# tx-warmer-smd.net
KiCad netlist of a schematic drawn in EAGLE
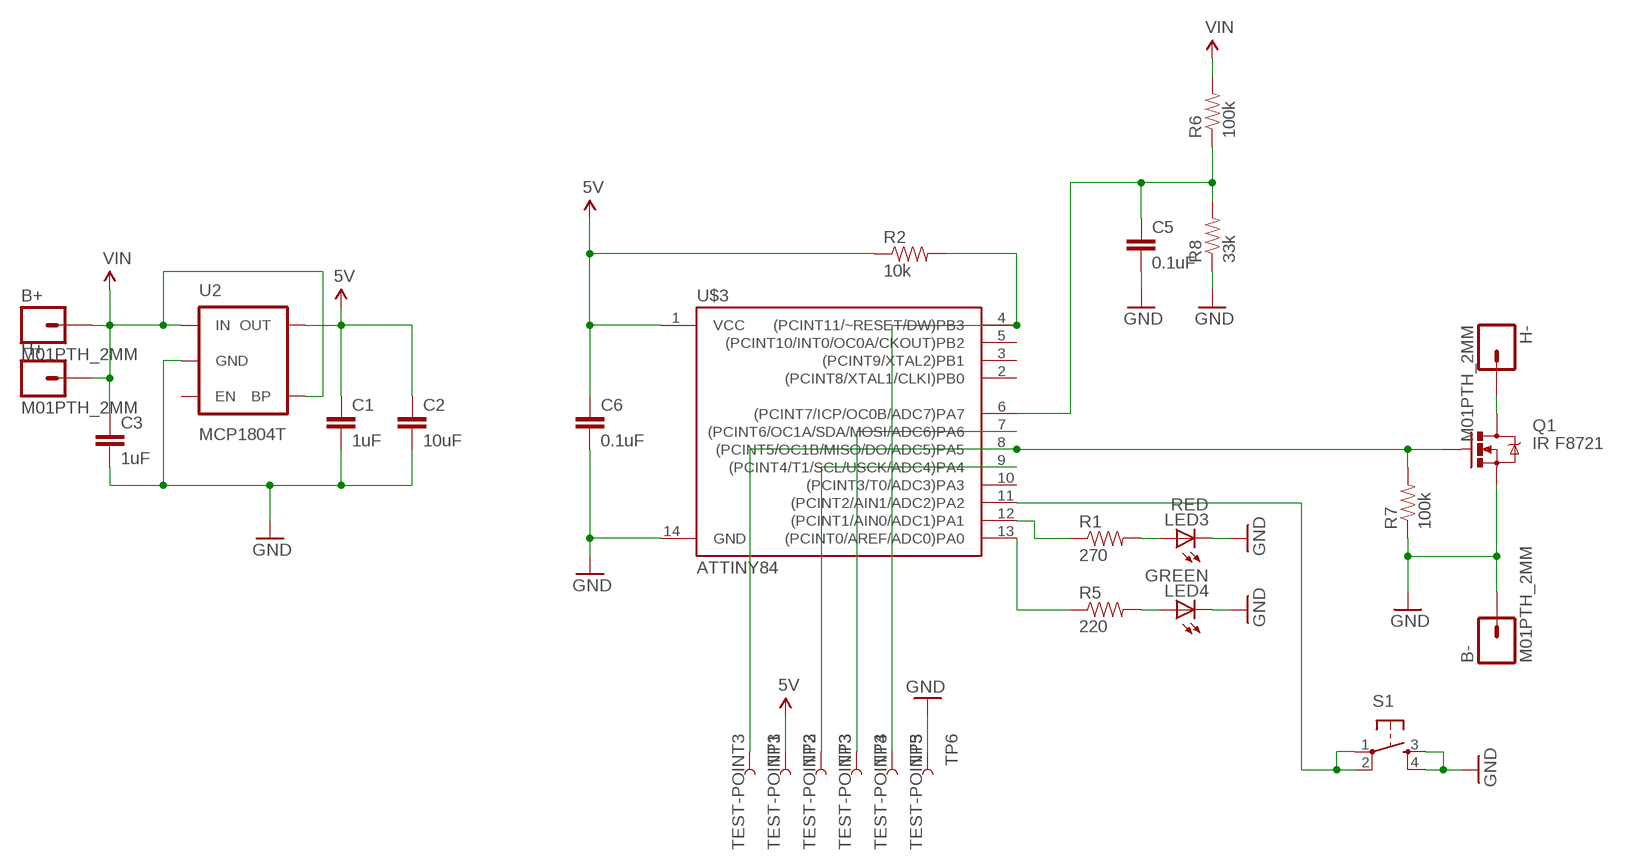
[diagram p0: schematic, sheet 1]

(export (version "E")
  (design (tool "Eeschema 10.0.6"))
  (components
    (comp (ref "B+")
      (value "M01PTH_2MM")
      (footprint "eagle-import:1X01_2MM")
      (libsource (lib "eagle-import") (part "M01PTH_2MM"))
    )
    (comp (ref "B-")
      (value "M01PTH_2MM")
      (footprint "eagle-import:1X01_2MM")
      (libsource (lib "eagle-import") (part "M01PTH_2MM"))
    )
    (comp (ref "C1")
      (value "1uF")
      (footprint "eagle-import:0805")
      (libsource (lib "eagle-import") (part "CAP0805"))
    )
    (comp (ref "C2")
      (value "10uF")
      (footprint "eagle-import:0805")
      (libsource (lib "eagle-import") (part "CAP0805"))
    )
    (comp (ref "C3")
      (value "1uF")
      (footprint "eagle-import:0805")
      (libsource (lib "eagle-import") (part "CAP0805"))
    )
    (comp (ref "C5")
      (value "0.1uF")
      (footprint "eagle-import:0805")
      (libsource (lib "eagle-import") (part "CAP0805"))
    )
    (comp (ref "C6")
      (value "0.1uF")
      (footprint "eagle-import:0805")
      (libsource (lib "eagle-import") (part "CAP0805"))
    )
    (comp (ref "H+")
      (value "M01PTH_2MM")
      (footprint "eagle-import:1X01_2MM")
      (libsource (lib "eagle-import") (part "M01PTH_2MM"))
    )
    (comp (ref "H-")
      (value "M01PTH_2MM")
      (footprint "eagle-import:1X01_2MM")
      (libsource (lib "eagle-import") (part "M01PTH_2MM"))
    )
    (comp (ref "LED3")
      (value "RED")
      (footprint "eagle-import:LED-1206")
      (libsource (lib "eagle-import") (part "LED1206"))
    )
    (comp (ref "LED4")
      (value "GREEN")
      (footprint "eagle-import:LED-1206")
      (libsource (lib "eagle-import") (part "LED1206"))
    )
    (comp (ref "Q1")
      (value "IR F8721")
      (footprint "eagle-import:SO08")
      (libsource (lib "eagle-import") (part "MOSFET-NCHANNELFDS6630A"))
    )
    (comp (ref "R1")
      (value "270")
      (footprint "eagle-import:0805")
      (libsource (lib "eagle-import") (part "RESISTOR0805-RES"))
    )
    (comp (ref "R2")
      (value "10k")
      (footprint "eagle-import:0805")
      (libsource (lib "eagle-import") (part "RESISTOR0805-RES"))
    )
    (comp (ref "R5")
      (value "220")
      (footprint "eagle-import:0805")
      (libsource (lib "eagle-import") (part "RESISTOR0805-RES"))
    )
    (comp (ref "R6")
      (value "100k")
      (footprint "eagle-import:0805")
      (libsource (lib "eagle-import") (part "RESISTOR0805-RES"))
    )
    (comp (ref "R7")
      (value "100k")
      (footprint "eagle-import:0805")
      (libsource (lib "eagle-import") (part "RESISTOR0805-RES"))
    )
    (comp (ref "R8")
      (value "33k")
      (footprint "eagle-import:0805")
      (libsource (lib "eagle-import") (part "RESISTOR0805-RES"))
    )
    (comp (ref "S1")
      (value "TAC_SWITCHSMD")
      (footprint "eagle-import:TACTILE_SWITCH_SMD")
      (libsource (lib "eagle-import") (part "TAC_SWITCHSMD"))
    )
    (comp (ref "TP1")
      (value "TEST-POINT3")
      (footprint "eagle-import:PAD.03X.03")
      (libsource (lib "eagle-import") (part "TEST-POINT3"))
    )
    (comp (ref "TP2")
      (value "TEST-POINT3")
      (footprint "eagle-import:PAD.03X.03")
      (libsource (lib "eagle-import") (part "TEST-POINT3"))
    )
    (comp (ref "TP3")
      (value "TEST-POINT3")
      (footprint "eagle-import:PAD.03X.03")
      (libsource (lib "eagle-import") (part "TEST-POINT3"))
    )
    (comp (ref "TP4")
      (value "TEST-POINT3")
      (footprint "eagle-import:PAD.03X.03")
      (libsource (lib "eagle-import") (part "TEST-POINT3"))
    )
    (comp (ref "TP5")
      (value "TEST-POINT3")
      (footprint "eagle-import:PAD.03X.03")
      (libsource (lib "eagle-import") (part "TEST-POINT3"))
    )
    (comp (ref "TP6")
      (value "TEST-POINT3")
      (footprint "eagle-import:PAD.03X.03")
      (libsource (lib "eagle-import") (part "TEST-POINT3"))
    )
    (comp (ref "U$3")
      (value "ATTINY84")
      (footprint "eagle-import:SO14")
      (libsource (lib "eagle-import") (part "ATTINY84"))
    )
    (comp (ref "U2")
      (value "MCP1804T")
      (footprint "eagle-import:SOT23-5")
      (libsource (lib "eagle-import") (part "V_REG_LDOSMD"))
    )
  )
  (nets
    (net (code "1") (name "5V") (class "Default")
      (node (ref "C1") (pin "1") (pinfunction "1_1") (pintype "passive"))
      (node (ref "C2") (pin "1") (pinfunction "1_1") (pintype "passive"))
      (node (ref "C6") (pin "1") (pinfunction "1_1") (pintype "passive"))
      (node (ref "R2") (pin "1") (pinfunction "1_1") (pintype "passive"))
      (node (ref "TP2") (pin "P$1") (pinfunction "1_P$1") (pintype "bidirectional"))
      (node (ref "U$3") (pin "1") (pinfunction "VCC_1") (pintype "bidirectional"))
      (node (ref "U2") (pin "5") (pinfunction "OUT_5") (pintype "passive"))
    )
    (net (code "2") (name "GND") (class "Default")
      (node (ref "B-") (pin "1") (pinfunction "1_1") (pintype "passive"))
      (node (ref "C1") (pin "2") (pinfunction "2_2") (pintype "passive"))
      (node (ref "C2") (pin "2") (pinfunction "2_2") (pintype "passive"))
      (node (ref "C3") (pin "2") (pinfunction "2_2") (pintype "passive"))
      (node (ref "C5") (pin "2") (pinfunction "2_2") (pintype "passive"))
      (node (ref "C6") (pin "2") (pinfunction "2_2") (pintype "passive"))
      (node (ref "LED3") (pin "C") (pinfunction "C_C") (pintype "passive"))
      (node (ref "LED4") (pin "C") (pinfunction "C_C") (pintype "passive"))
      (node (ref "Q1") (pin "1") (pinfunction "S_1") (pintype "passive"))
      (node (ref "Q1") (pin "2") (pinfunction "S_2") (pintype "passive"))
      (node (ref "Q1") (pin "3") (pinfunction "S_3") (pintype "passive"))
      (node (ref "R7") (pin "1") (pinfunction "1_1") (pintype "passive"))
      (node (ref "R8") (pin "1") (pinfunction "1_1") (pintype "passive"))
      (node (ref "S1") (pin "3") (pinfunction "3_3") (pintype "passive"))
      (node (ref "S1") (pin "4") (pinfunction "4_4") (pintype "passive"))
      (node (ref "TP6") (pin "P$1") (pinfunction "1_P$1") (pintype "bidirectional"))
      (node (ref "U$3") (pin "14") (pinfunction "GND_14") (pintype "bidirectional"))
      (node (ref "U2") (pin "2") (pinfunction "GND_2") (pintype "input"))
    )
    (net (code "3") (name "Net-(H--Pad1)") (class "Default")
      (node (ref "H-") (pin "1") (pinfunction "1_1") (pintype "passive"))
      (node (ref "Q1") (pin "5") (pinfunction "D_5") (pintype "passive"))
      (node (ref "Q1") (pin "6") (pinfunction "D_6") (pintype "passive"))
      (node (ref "Q1") (pin "7") (pinfunction "D_7") (pintype "passive"))
      (node (ref "Q1") (pin "8") (pinfunction "D_8") (pintype "passive"))
    )
    (net (code "4") (name "Net-(LED3-PadA)") (class "Default")
      (node (ref "LED3") (pin "A") (pinfunction "A_A") (pintype "passive"))
      (node (ref "R1") (pin "2") (pinfunction "2_2") (pintype "passive"))
    )
    (net (code "5") (name "Net-(LED4-PadA)") (class "Default")
      (node (ref "LED4") (pin "A") (pinfunction "A_A") (pintype "passive"))
      (node (ref "R5") (pin "2") (pinfunction "2_2") (pintype "passive"))
    )
    (net (code "6") (name "Net-(Q1-G)") (class "Default")
      (node (ref "Q1") (pin "4") (pinfunction "G_4") (pintype "passive"))
      (node (ref "R7") (pin "2") (pinfunction "2_2") (pintype "passive"))
      (node (ref "TP1") (pin "P$1") (pinfunction "1_P$1") (pintype "bidirectional"))
      (node (ref "U$3") (pin "8") (pinfunction "(PCINT5/OC1B/MISO/DO/ADC5)PA5_8") (pintype "bidirectional"))
    )
    (net (code "7") (name "Net-(TP3-1)") (class "Default")
      (node (ref "TP3") (pin "P$1") (pinfunction "1_P$1") (pintype "bidirectional"))
      (node (ref "U$3") (pin "9") (pinfunction "(PCINT4/T1/SCL/USCK/ADC4)PA4_9") (pintype "bidirectional"))
    )
    (net (code "8") (name "Net-(TP4-1)") (class "Default")
      (node (ref "TP4") (pin "P$1") (pinfunction "1_P$1") (pintype "bidirectional"))
      (node (ref "U$3") (pin "7") (pinfunction "(PCINT6/OC1A/SDA/MOSI/ADC6)PA6_7") (pintype "bidirectional"))
    )
    (net (code "9") (name "Net-(TP5-1)") (class "Default")
      (node (ref "R2") (pin "2") (pinfunction "2_2") (pintype "passive"))
      (node (ref "TP5") (pin "P$1") (pinfunction "1_P$1") (pintype "bidirectional"))
      (node (ref "U$3") (pin "4") (pinfunction "(PCINT11/~{RESET/DW})PB3_4") (pintype "bidirectional"))
    )
    (net (code "10") (name "Net-(U$3-(PCINT0{slash}AREF{slash}ADC0)PA0)") (class "Default")
      (node (ref "R5") (pin "1") (pinfunction "1_1") (pintype "passive"))
      (node (ref "U$3") (pin "13") (pinfunction "(PCINT0/AREF/ADC0)PA0_13") (pintype "bidirectional"))
    )
    (net (code "11") (name "Net-(U$3-(PCINT1{slash}AIN0{slash}ADC1)PA1)") (class "Default")
      (node (ref "R1") (pin "1") (pinfunction "1_1") (pintype "passive"))
      (node (ref "U$3") (pin "12") (pinfunction "(PCINT1/AIN0/ADC1)PA1_12") (pintype "bidirectional"))
    )
    (net (code "12") (name "Net-(U$3-(PCINT2{slash}AIN1{slash}ADC2)PA2)") (class "Default")
      (node (ref "S1") (pin "1") (pinfunction "1_1") (pintype "passive"))
      (node (ref "S1") (pin "2") (pinfunction "2_2") (pintype "passive"))
      (node (ref "U$3") (pin "11") (pinfunction "(PCINT2/AIN1/ADC2)PA2_11") (pintype "bidirectional"))
    )
    (net (code "13") (name "Net-(U$3-(PCINT7{slash}ICP{slash}OC0B{slash}ADC7)PA7)") (class "Default")
      (node (ref "C5") (pin "1") (pinfunction "1_1") (pintype "passive"))
      (node (ref "R6") (pin "1") (pinfunction "1_1") (pintype "passive"))
      (node (ref "R8") (pin "2") (pinfunction "2_2") (pintype "passive"))
      (node (ref "U$3") (pin "6") (pinfunction "(PCINT7/ICP/OC0B/ADC7)PA7_6") (pintype "bidirectional"))
    )
    (net (code "14") (name "VIN") (class "Default")
      (node (ref "B+") (pin "1") (pinfunction "1_1") (pintype "passive"))
      (node (ref "C3") (pin "1") (pinfunction "1_1") (pintype "passive"))
      (node (ref "H+") (pin "1") (pinfunction "1_1") (pintype "passive"))
      (node (ref "R6") (pin "2") (pinfunction "2_2") (pintype "passive"))
      (node (ref "U2") (pin "1") (pinfunction "IN_1") (pintype "input"))
      (node (ref "U2") (pin "4") (pinfunction "BP_4") (pintype "input"))
    )
    (net (code "15") (name "unconnected-(U$3-(PCINT3{slash}T0{slash}ADC3)PA3-Pad10)") (class "Default")
      (node (ref "U$3") (pin "10") (pinfunction "(PCINT3/T0/ADC3)PA3_10") (pintype "bidirectional"))
    )
    (net (code "16") (name "unconnected-(U$3-(PCINT8{slash}XTAL1{slash}CLKI)PB0-Pad2)") (class "Default")
      (node (ref "U$3") (pin "2") (pinfunction "(PCINT8/XTAL1/CLKI)PB0_2") (pintype "bidirectional"))
    )
    (net (code "17") (name "unconnected-(U$3-(PCINT9{slash}XTAL2)PB1-Pad3)") (class "Default")
      (node (ref "U$3") (pin "3") (pinfunction "(PCINT9/XTAL2)PB1_3") (pintype "bidirectional"))
    )
    (net (code "18") (name "unconnected-(U$3-(PCINT10{slash}INT0{slash}OC0A{slash}CKOUT)PB2-Pad5)") (class "Default")
      (node (ref "U$3") (pin "5") (pinfunction "(PCINT10/INT0/OC0A/CKOUT)PB2_5") (pintype "bidirectional"))
    )
    (net (code "19") (name "unconnected-(U2-EN-Pad3)") (class "Default")
      (node (ref "U2") (pin "3") (pinfunction "EN_3") (pintype "input"))
    )
  )
)
